# AFE.net
KiCad netlist of a schematic drawn in Altium Designer
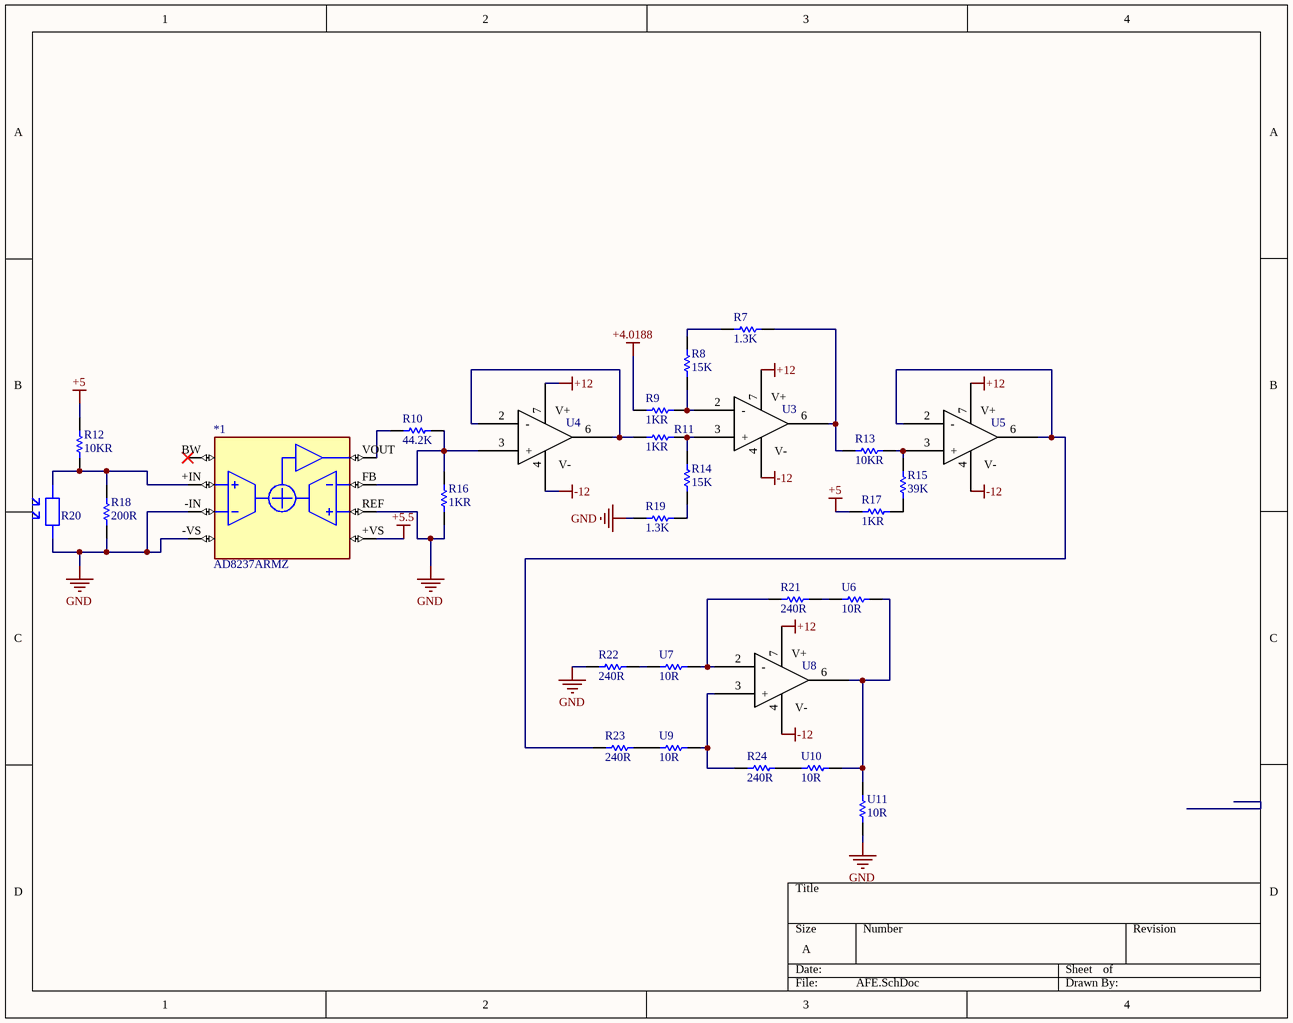
[diagram p0: AFE.SchDoc]

(export (version "E")
  (design (tool "Eeschema 10.0.6"))
  (components
    (comp (ref "*1")
      (value "AD8237ARMZ")
      (footprint "AD8237ARMZ")
      (libsource (lib "Schlib1") (part "AD8237ARMZ"))
    )
    (comp (ref "R7")
      (value "1.3K")
      (footprint "RES_0805")
      (description "Điện Trở 1.3 KOhm 0805 5%")
      (libsource (lib "Schlib1") (part "RES_1.3K_0805"))
    )
    (comp (ref "R8")
      (value "15K")
      (footprint "RES_0805")
      (description "Điện Trở 15 KOhm 0805 1%")
      (libsource (lib "Schlib1") (part "RES_15K_0805"))
    )
    (comp (ref "R9")
      (value "1KR")
      (footprint "RES_0805")
      (description "Điện Trở 1 KOhm 0805 1%")
      (libsource (lib "Schlib1") (part "RES_1K_0805"))
    )
    (comp (ref "R10")
      (value "44.2K")
      (footprint "RES_0805")
      (description "Điện Trở 44.2 KOhm 0805 1%")
      (libsource (lib "Schlib1") (part "RES_44.2K_0805"))
    )
    (comp (ref "R11")
      (value "1KR")
      (footprint "RES_0805")
      (description "Điện Trở 1 KOhm 0805 1%")
      (libsource (lib "Schlib1") (part "RES_1K_0805"))
    )
    (comp (ref "R12")
      (value "10KR")
      (footprint "RES_0805")
      (description "Điện Trở 10 KOhm 0805 1%")
      (libsource (lib "Schlib1") (part "RES_10K_0805"))
    )
    (comp (ref "R13")
      (value "10KR")
      (footprint "RES_0805")
      (description "Điện Trở 10 KOhm 0805 1%")
      (libsource (lib "Schlib1") (part "RES_10K_0805"))
    )
    (comp (ref "R14")
      (value "15K")
      (footprint "RES_0805")
      (description "Điện Trở 15 KOhm 0805 1%")
      (libsource (lib "Schlib1") (part "RES_15K_0805"))
    )
    (comp (ref "R15")
      (value "39K")
      (footprint "RES_0805")
      (description "Điện Trở 39 KOhm 0805 1%")
      (libsource (lib "Schlib1") (part "RES_39K_0805"))
    )
    (comp (ref "R16")
      (value "1KR")
      (footprint "RES_0805")
      (description "Điện Trở 1 KOhm 0805 1%")
      (libsource (lib "Schlib1") (part "RES_1K_0805"))
    )
    (comp (ref "R17")
      (value "1KR")
      (footprint "RES_0805")
      (description "Điện Trở 1 KOhm 0805 1%")
      (libsource (lib "Schlib1") (part "RES_1K_0805"))
    )
    (comp (ref "R18")
      (value "200R")
      (footprint "RES_0805")
      (description "Điện Trở 220 Ohm 0805 1%")
      (libsource (lib "Schlib1") (part "RES_200_0805"))
    )
    (comp (ref "R19")
      (value "1.3K")
      (footprint "RES_0805")
      (description "Điện Trở 1.3 KOhm 0805 5%")
      (libsource (lib "Schlib1") (part "RES_1.3K_0805"))
    )
    (comp (ref "R20")
      (value "GL5528")
      (footprint "GL5528")
      (description "CDS PHOTORESISTOR")
      (libsource (lib "Schlib1") (part "GL5528"))
    )
    (comp (ref "R21")
      (value "240R")
      (description "Điện Trở 240 Ohm 0805 5%")
      (libsource (lib "Schlib1") (part "RES_240R_0805"))
    )
    (comp (ref "R22")
      (value "240R")
      (description "Điện Trở 240 Ohm 0805 5%")
      (libsource (lib "Schlib1") (part "RES_240R_0805"))
    )
    (comp (ref "R23")
      (value "240R")
      (description "Điện Trở 240 Ohm 0805 5%")
      (libsource (lib "Schlib1") (part "RES_240R_0805"))
    )
    (comp (ref "R24")
      (value "240R")
      (description "Điện Trở 240 Ohm 0805 5%")
      (libsource (lib "Schlib1") (part "RES_240R_0805"))
    )
    (comp (ref "U3")
      (value "OPA188AID")
      (footprint "OPA")
      (description "IC OPAMP ZERO-DRIFT 1 CIRC 8SOIC")
      (libsource (lib "Schlib1") (part "OPA188AID"))
    )
    (comp (ref "U4")
      (value "OPA188AID")
      (footprint "OPA")
      (description "IC OPAMP ZERO-DRIFT 1 CIRC 8SOIC")
      (libsource (lib "Schlib1") (part "OPA188AID"))
    )
    (comp (ref "U5")
      (value "OPA188AID")
      (footprint "OPA")
      (description "IC OPAMP ZERO-DRIFT 1 CIRC 8SOIC")
      (libsource (lib "Schlib1") (part "OPA188AID"))
    )
    (comp (ref "U6")
      (value "10R")
      (footprint "RES_0805")
      (description "Điện Trở 10 Ohm 0805 1%")
      (libsource (lib "Schlib1") (part "RES_10R_0805"))
    )
    (comp (ref "U7")
      (value "10R")
      (footprint "RES_0805")
      (description "Điện Trở 10 Ohm 0805 1%")
      (libsource (lib "Schlib1") (part "RES_10R_0805"))
    )
    (comp (ref "U8")
      (value "OPA188AID")
      (footprint "OPA")
      (description "IC OPAMP ZERO-DRIFT 1 CIRC 8SOIC")
      (libsource (lib "Schlib1") (part "OPA188AID"))
    )
    (comp (ref "U9")
      (value "10R")
      (footprint "RES_0805")
      (description "Điện Trở 10 Ohm 0805 1%")
      (libsource (lib "Schlib1") (part "RES_10R_0805"))
    )
    (comp (ref "U10")
      (value "10R")
      (footprint "RES_0805")
      (description "Điện Trở 10 Ohm 0805 1%")
      (libsource (lib "Schlib1") (part "RES_10R_0805"))
    )
    (comp (ref "U11")
      (value "10R")
      (footprint "RES_0805")
      (description "Điện Trở 10 Ohm 0805 1%")
      (libsource (lib "Schlib1") (part "RES_10R_0805"))
    )
  )
  (nets
    (net (code "1") (name "+4.0188") (class "Default")
      (node (ref "R9") (pin "1") (pinfunction "1_1") (pintype "passive"))
    )
    (net (code "2") (name "+5") (class "Default")
      (node (ref "R12") (pin "2") (pinfunction "2_2") (pintype "passive"))
      (node (ref "R17") (pin "1") (pinfunction "1_1") (pintype "passive"))
    )
    (net (code "3") (name "+5.5") (class "Default")
      (node (ref "*1") (pin "+VS") (pinfunction "+VS_+VS") (pintype "bidirectional"))
    )
    (net (code "4") (name "+12") (class "Default")
      (node (ref "U3") (pin "7") (pinfunction "VCC_7") (pintype "passive"))
      (node (ref "U4") (pin "7") (pinfunction "VCC_7") (pintype "passive"))
      (node (ref "U5") (pin "7") (pinfunction "VCC_7") (pintype "passive"))
      (node (ref "U8") (pin "7") (pinfunction "VCC_7") (pintype "passive"))
    )
    (net (code "5") (name "-12") (class "Default")
      (node (ref "U3") (pin "4") (pinfunction "GND_4") (pintype "passive"))
      (node (ref "U4") (pin "4") (pinfunction "GND_4") (pintype "passive"))
      (node (ref "U5") (pin "4") (pinfunction "GND_4") (pintype "passive"))
      (node (ref "U8") (pin "4") (pinfunction "GND_4") (pintype "passive"))
    )
    (net (code "6") (name "GND") (class "Default")
      (node (ref "*1") (pin "-IN") (pinfunction "-IN_-IN") (pintype "bidirectional"))
      (node (ref "*1") (pin "-VS") (pinfunction "-VS_-VS") (pintype "bidirectional"))
      (node (ref "*1") (pin "REF") (pinfunction "REF_REF") (pintype "bidirectional"))
      (node (ref "R16") (pin "1") (pinfunction "1_1") (pintype "passive"))
      (node (ref "R18") (pin "1") (pinfunction "1_1") (pintype "passive"))
      (node (ref "R19") (pin "2") (pinfunction "2_2") (pintype "passive"))
      (node (ref "R20") (pin "4") (pinfunction "4_4") (pintype "passive"))
      (node (ref "R22") (pin "1") (pinfunction "1_1") (pintype "passive"))
      (node (ref "U11") (pin "1") (pinfunction "1_1") (pintype "passive"))
    )
    (net (code "7") (name "Net-(*1-Pad+IN)") (class "Default")
      (node (ref "*1") (pin "+IN") (pinfunction "+IN_+IN") (pintype "bidirectional"))
      (node (ref "R12") (pin "1") (pinfunction "1_1") (pintype "passive"))
      (node (ref "R18") (pin "2") (pinfunction "2_2") (pintype "passive"))
      (node (ref "R20") (pin "5") (pinfunction "5_5") (pintype "passive"))
    )
    (net (code "8") (name "Net-(*1-PadVOUT)") (class "Default")
      (node (ref "*1") (pin "VOUT") (pinfunction "VOUT_VOUT") (pintype "bidirectional"))
      (node (ref "R10") (pin "1") (pinfunction "1_1") (pintype "passive"))
    )
    (net (code "9") (name "Net-(R7-Pad1)") (class "Default")
      (node (ref "R7") (pin "1") (pinfunction "1_1") (pintype "passive"))
      (node (ref "R8") (pin "2") (pinfunction "2_2") (pintype "passive"))
    )
    (net (code "10") (name "Net-(R14-Pad1)") (class "Default")
      (node (ref "R14") (pin "1") (pinfunction "1_1") (pintype "passive"))
      (node (ref "R19") (pin "1") (pinfunction "1_1") (pintype "passive"))
    )
    (net (code "11") (name "Net-(R15-Pad2)") (class "Default")
      (node (ref "R15") (pin "2") (pinfunction "2_2") (pintype "passive"))
      (node (ref "R17") (pin "2") (pinfunction "2_2") (pintype "passive"))
    )
    (net (code "12") (name "Net-(R21-Pad2)") (class "Default")
      (node (ref "R21") (pin "2") (pinfunction "2_2") (pintype "passive"))
      (node (ref "U6") (pin "1") (pinfunction "1_1") (pintype "passive"))
    )
    (net (code "13") (name "Net-(R22-Pad2)") (class "Default")
      (node (ref "R22") (pin "2") (pinfunction "2_2") (pintype "passive"))
      (node (ref "U7") (pin "1") (pinfunction "1_1") (pintype "passive"))
    )
    (net (code "14") (name "Net-(R23-Pad2)") (class "Default")
      (node (ref "R23") (pin "2") (pinfunction "2_2") (pintype "passive"))
      (node (ref "U9") (pin "1") (pinfunction "1_1") (pintype "passive"))
    )
    (net (code "15") (name "Net-(R24-Pad2)") (class "Default")
      (node (ref "R24") (pin "2") (pinfunction "2_2") (pintype "passive"))
      (node (ref "U10") (pin "1") (pinfunction "1_1") (pintype "passive"))
    )
    (net (code "16") (name "Net-(U3-+)") (class "Default")
      (node (ref "R11") (pin "2") (pinfunction "2_2") (pintype "passive"))
      (node (ref "R14") (pin "2") (pinfunction "2_2") (pintype "passive"))
      (node (ref "U3") (pin "3") (pinfunction "+_3") (pintype "passive"))
    )
    (net (code "17") (name "Net-(U3--)") (class "Default")
      (node (ref "R8") (pin "1") (pinfunction "1_1") (pintype "passive"))
      (node (ref "R9") (pin "2") (pinfunction "2_2") (pintype "passive"))
      (node (ref "U3") (pin "2") (pinfunction "-_2") (pintype "passive"))
    )
    (net (code "18") (name "Net-(U3-OUT_1)") (class "Default")
      (node (ref "R13") (pin "1") (pinfunction "1_1") (pintype "passive"))
      (node (ref "R7") (pin "2") (pinfunction "2_2") (pintype "passive"))
      (node (ref "U3") (pin "6") (pinfunction "OUT_1_6") (pintype "passive"))
    )
    (net (code "19") (name "Net-(U4-+)") (class "Default")
      (node (ref "*1") (pin "FB") (pinfunction "FB_FB") (pintype "bidirectional"))
      (node (ref "R10") (pin "2") (pinfunction "2_2") (pintype "passive"))
      (node (ref "R16") (pin "2") (pinfunction "2_2") (pintype "passive"))
      (node (ref "U4") (pin "3") (pinfunction "+_3") (pintype "passive"))
    )
    (net (code "20") (name "Net-(U4--)") (class "Default")
      (node (ref "R11") (pin "1") (pinfunction "1_1") (pintype "passive"))
      (node (ref "U4") (pin "2") (pinfunction "-_2") (pintype "passive"))
      (node (ref "U4") (pin "6") (pinfunction "OUT_1_6") (pintype "passive"))
    )
    (net (code "21") (name "Net-(U5-+)") (class "Default")
      (node (ref "R13") (pin "2") (pinfunction "2_2") (pintype "passive"))
      (node (ref "R15") (pin "1") (pinfunction "1_1") (pintype "passive"))
      (node (ref "U5") (pin "3") (pinfunction "+_3") (pintype "passive"))
    )
    (net (code "22") (name "Net-(U5--)") (class "Default")
      (node (ref "R23") (pin "1") (pinfunction "1_1") (pintype "passive"))
      (node (ref "U5") (pin "2") (pinfunction "-_2") (pintype "passive"))
      (node (ref "U5") (pin "6") (pinfunction "OUT_1_6") (pintype "passive"))
    )
    (net (code "23") (name "Net-(U8-+)") (class "Default")
      (node (ref "R24") (pin "1") (pinfunction "1_1") (pintype "passive"))
      (node (ref "U8") (pin "3") (pinfunction "+_3") (pintype "passive"))
      (node (ref "U9") (pin "2") (pinfunction "2_2") (pintype "passive"))
    )
    (net (code "24") (name "Net-(U8--)") (class "Default")
      (node (ref "R21") (pin "1") (pinfunction "1_1") (pintype "passive"))
      (node (ref "U7") (pin "2") (pinfunction "2_2") (pintype "passive"))
      (node (ref "U8") (pin "2") (pinfunction "-_2") (pintype "passive"))
    )
    (net (code "25") (name "Net-(U8-OUT_1)") (class "Default")
      (node (ref "U10") (pin "2") (pinfunction "2_2") (pintype "passive"))
      (node (ref "U11") (pin "2") (pinfunction "2_2") (pintype "passive"))
      (node (ref "U6") (pin "2") (pinfunction "2_2") (pintype "passive"))
      (node (ref "U8") (pin "6") (pinfunction "OUT_1_6") (pintype "passive"))
    )
    (net (code "26") (name "unconnected-(*1-PadBW)") (class "Default")
      (node (ref "*1") (pin "BW") (pinfunction "BW_BW") (pintype "bidirectional+no_connect"))
    )
  )
)
